# control_bat.net
KiCad netlist of a schematic drawn in EAGLE
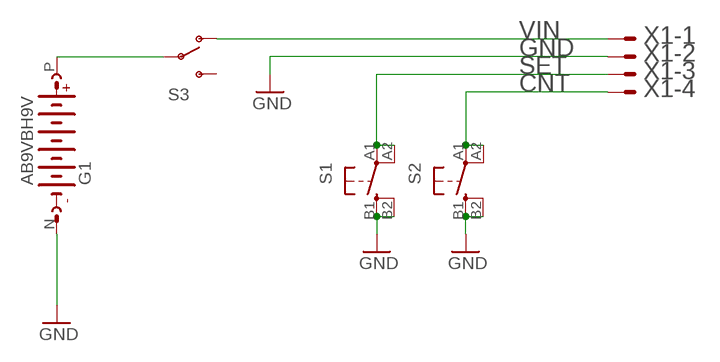
[diagram p0: schematic, sheet 1]

(export (version "E")
  (design (tool "Eeschema 10.0.6"))
  (components
    (comp (ref "G1")
      (value "AB9VBH9V")
      (footprint "eagle-import:BH9V-PC-ND")
      (libsource (lib "eagle-import") (part "AB9VBH9V"))
    )
    (comp (ref "S1")
      (value "TAC_SWITCHD6F")
      (footprint "eagle-import:D6F")
      (libsource (lib "eagle-import") (part "TAC_SWITCHD6F"))
    )
    (comp (ref "S2")
      (value "TAC_SWITCHD6F")
      (footprint "eagle-import:D6F")
      (libsource (lib "eagle-import") (part "TAC_SWITCHD6F"))
    )
    (comp (ref "S3")
      (value "SWITCH-SPST")
      (footprint "eagle-import:EG1270")
      (libsource (lib "eagle-import") (part "SWITCH-SPST"))
    )
    (comp (ref "X1")
      (value "DF13-4P-1.25V(50)")
      (footprint "eagle-import:53398-04")
      (libsource (lib "eagle-import") (part "53?-04398"))
    )
  )
  (nets
    (net (code "1") (name "/CNT") (class "Default")
      (node (ref "S2") (pin "A1") (pinfunction "1_A1") (pintype "passive"))
      (node (ref "S2") (pin "A2") (pinfunction "2_A2") (pintype "passive"))
      (node (ref "X1") (pin "4") (pinfunction "S_4") (pintype "passive"))
    )
    (net (code "2") (name "/SET") (class "Default")
      (node (ref "S1") (pin "A1") (pinfunction "1_A1") (pintype "passive"))
      (node (ref "S1") (pin "A2") (pinfunction "2_A2") (pintype "passive"))
      (node (ref "X1") (pin "3") (pinfunction "S_3") (pintype "passive"))
    )
    (net (code "3") (name "/VIN") (class "Default")
      (node (ref "S3") (pin "P$1") (pinfunction "O_P$1") (pintype "passive"))
      (node (ref "X1") (pin "1") (pinfunction "S_1") (pintype "passive"))
    )
    (net (code "4") (name "GND") (class "Default")
      (node (ref "G1") (pin "N") (pinfunction "-_N") (pintype "passive"))
      (node (ref "S1") (pin "B1") (pinfunction "3_B1") (pintype "passive"))
      (node (ref "S1") (pin "B2") (pinfunction "4_B2") (pintype "passive"))
      (node (ref "S2") (pin "B1") (pinfunction "3_B1") (pintype "passive"))
      (node (ref "S2") (pin "B2") (pinfunction "4_B2") (pintype "passive"))
      (node (ref "X1") (pin "2") (pinfunction "S_2") (pintype "passive"))
    )
    (net (code "5") (name "Net-(G1-+)") (class "Default")
      (node (ref "G1") (pin "P") (pinfunction "+_P") (pintype "passive"))
      (node (ref "S3") (pin "P$2") (pinfunction "P_P$2") (pintype "passive"))
    )
    (net (code "6") (name "unconnected-(S3-S-PadP$3)") (class "Default")
      (node (ref "S3") (pin "P$3") (pinfunction "S_P$3") (pintype "passive"))
    )
  )
)
